# Sheet1.net
KiCad netlist of a schematic drawn in Altium Designer
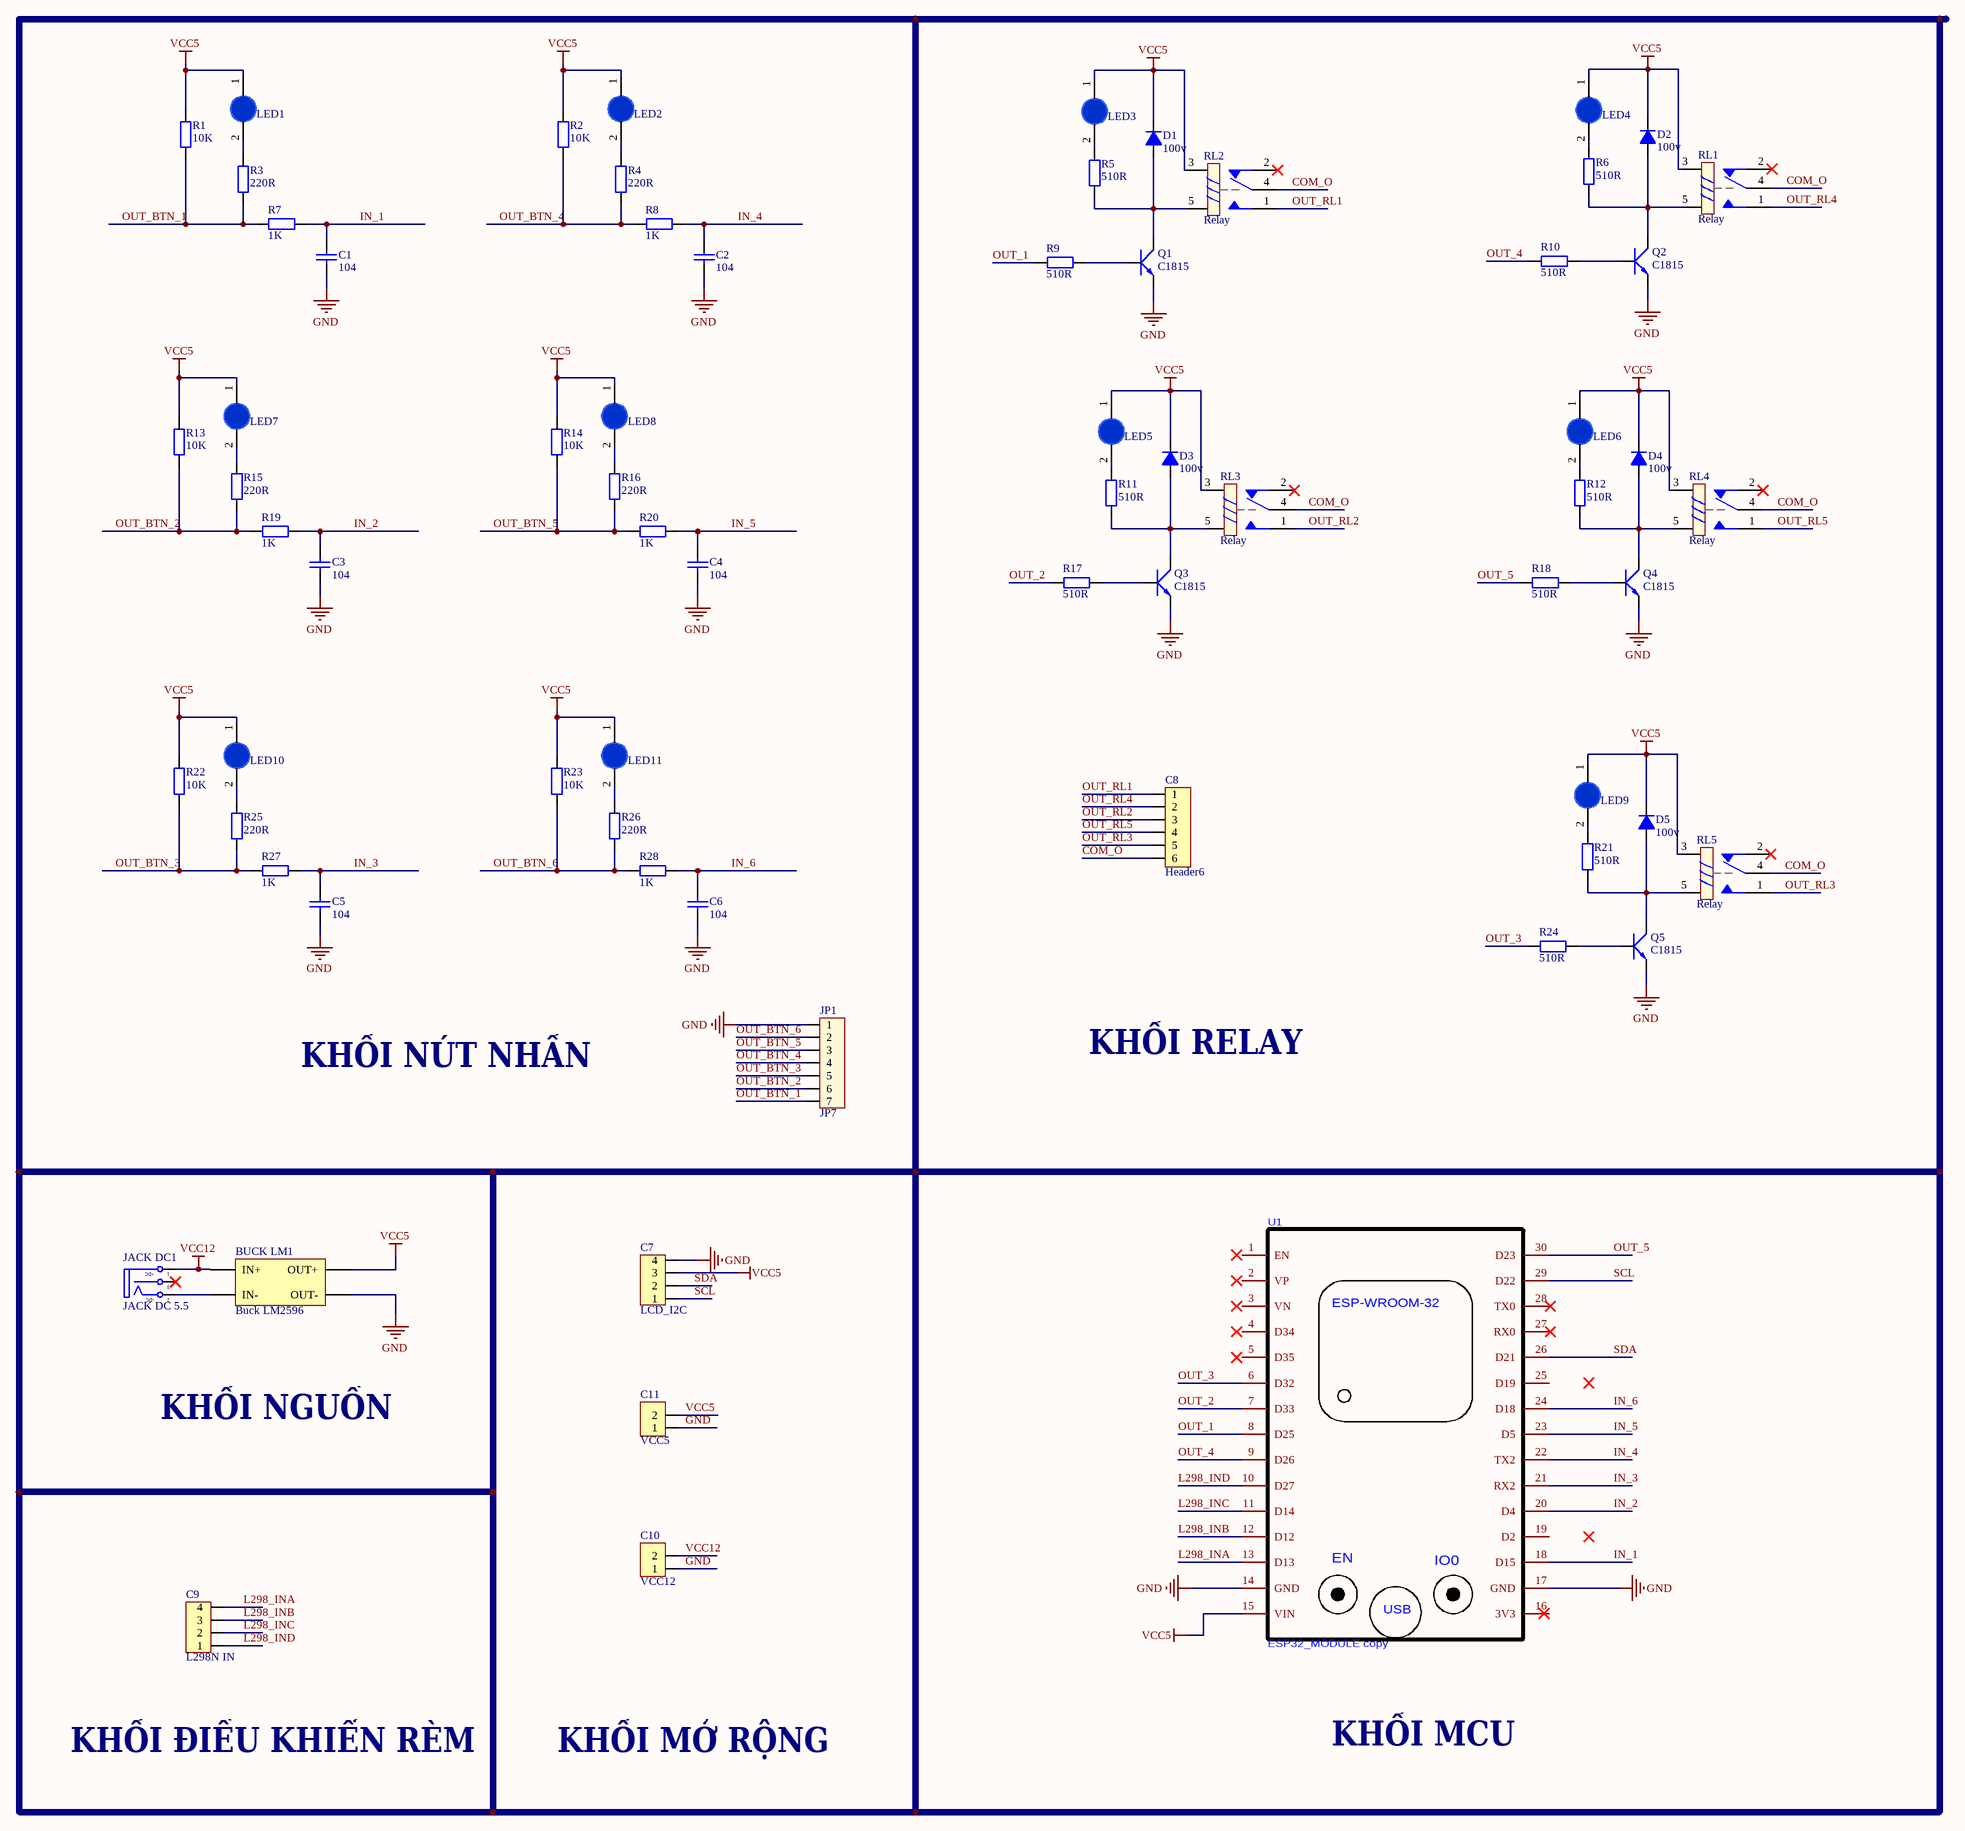
[diagram p0: Sheet1.SchDoc]

(export (version "E")
  (design (tool "Eeschema 10.0.6"))
  (components
    (comp (ref "BUCK LM1")
      (value "Buck LM2596")
      (footprint "BUCK LM2596")
      (libsource (lib "myLib_v1") (part "Buck LM2596"))
    )
    (comp (ref "C1")
      (value "104")
      (footprint "tu gom")
      (description "Cắm")
      (libsource (lib "Altium_Lib_by_KhueNguyenCreator") (part "Tu gom 104 50V"))
    )
    (comp (ref "C2")
      (value "104")
      (footprint "tu gom")
      (description "Cắm")
      (libsource (lib "Altium_Lib_by_KhueNguyenCreator") (part "Tu gom 104 50V"))
    )
    (comp (ref "C3")
      (value "104")
      (footprint "tu gom")
      (description "Cắm")
      (libsource (lib "Altium_Lib_by_KhueNguyenCreator") (part "Tu gom 104 50V"))
    )
    (comp (ref "C4")
      (value "104")
      (footprint "tu gom")
      (description "Cắm")
      (libsource (lib "Altium_Lib_by_KhueNguyenCreator") (part "Tu gom 104 50V"))
    )
    (comp (ref "C5")
      (value "104")
      (footprint "tu gom")
      (description "Cắm")
      (libsource (lib "Altium_Lib_by_KhueNguyenCreator") (part "Tu gom 104 50V"))
    )
    (comp (ref "C6")
      (value "104")
      (footprint "tu gom")
      (description "Cắm")
      (libsource (lib "Altium_Lib_by_KhueNguyenCreator") (part "Tu gom 104 50V"))
    )
    (comp (ref "C7")
      (value "LCD_I2C")
      (footprint "Header4")
      (description "Header IDC, 4 x 1 Pin Vertical 2.54mm Pitch (Non-Boxed, Male)")
      (fields
        (field (name "MANUFACTURER") "Würth Elektronik eiSos GmbH")
        (field (name "PARTNO") "613002143121")
        (field (name "CREATED BY") "Karrer Zheng")
      )
      (libsource (lib "myLib_v1") (part "Header4"))
    )
    (comp (ref "C8")
      (value "Header6")
      (footprint "Header6")
      (description "Header IDC, 6 x 1 Pin Vertical 2.54mm Pitch (Non-Boxed, Male)")
      (fields
        (field (name "MANUFACTURER") "Würth Elektronik eiSos GmbH")
        (field (name "PARTNO") "613002143121")
        (field (name "CREATED BY") "Karrer Zheng")
      )
      (libsource (lib "myLib_v1") (part "Header6"))
    )
    (comp (ref "C9")
      (value "L298N IN")
      (footprint "Header4")
      (description "Header IDC, 4 x 1 Pin Vertical 2.54mm Pitch (Non-Boxed, Male)")
      (fields
        (field (name "MANUFACTURER") "Würth Elektronik eiSos GmbH")
        (field (name "PARTNO") "613002143121")
        (field (name "CREATED BY") "Karrer Zheng")
      )
      (libsource (lib "myLib_v1") (part "Header4"))
    )
    (comp (ref "C10")
      (value "VCC12")
      (footprint "Header2")
      (description "Header IDC, 2 x 1 Pin Vertical 2.54mm Pitch (Non-Boxed, Male)")
      (fields
        (field (name "MANUFACTURER") "Würth Elektronik eiSos GmbH")
        (field (name "PARTNO") "613002143121")
        (field (name "CREATED BY") "Karrer Zheng")
      )
      (libsource (lib "myLib_v1") (part "Header2"))
    )
    (comp (ref "C11")
      (value "VCC5")
      (footprint "Header2")
      (description "Header IDC, 2 x 1 Pin Vertical 2.54mm Pitch (Non-Boxed, Male)")
      (fields
        (field (name "MANUFACTURER") "Würth Elektronik eiSos GmbH")
        (field (name "PARTNO") "613002143121")
        (field (name "CREATED BY") "Karrer Zheng")
      )
      (libsource (lib "myLib_v1") (part "Header2"))
    )
    (comp (ref "D1")
      (value "100v")
      (footprint "DIODE 0.5A")
      (description "Cắm")
      (libsource (lib "Altium_Lib_by_KhueNguyenCreator") (part "Diode 1N4148"))
    )
    (comp (ref "D2")
      (value "100v")
      (footprint "DIODE 0.5A")
      (description "Cắm")
      (libsource (lib "Altium_Lib_by_KhueNguyenCreator") (part "Diode 1N4148"))
    )
    (comp (ref "D3")
      (value "100v")
      (footprint "DIODE 0.5A")
      (description "Cắm")
      (libsource (lib "Altium_Lib_by_KhueNguyenCreator") (part "Diode 1N4148"))
    )
    (comp (ref "D4")
      (value "100v")
      (footprint "DIODE 0.5A")
      (description "Cắm")
      (libsource (lib "Altium_Lib_by_KhueNguyenCreator") (part "Diode 1N4148"))
    )
    (comp (ref "D5")
      (value "100v")
      (footprint "DIODE 0.5A")
      (description "Cắm")
      (libsource (lib "Altium_Lib_by_KhueNguyenCreator") (part "Diode 1N4148"))
    )
    (comp (ref "JACK DC1")
      (value "JACK DC 5.5")
      (footprint "JACK DC 5.5")
      (libsource (lib "Altium_Lib_by_KhueNguyenCreator") (part "JACK DC 5.5"))
    )
    (comp (ref "JP1")
      (value "JP7")
      (footprint "Header7")
      (description "Connector 7")
      (libsource (lib "myLib_v1") (part "Header7"))
    )
    (comp (ref "LED1")
      (value "LED 3mm")
      (footprint "LED-3MM-BLUE")
      (description "Cắm")
      (libsource (lib "myLib_v1") (part "LED 3mm Xanh Duong"))
    )
    (comp (ref "LED2")
      (value "LED 3mm")
      (footprint "LED-3MM-BLUE")
      (description "Cắm")
      (libsource (lib "myLib_v1") (part "LED 3mm Xanh Duong"))
    )
    (comp (ref "LED3")
      (value "LED 3mm")
      (footprint "LED-3MM-BLUE")
      (description "Cắm")
      (libsource (lib "myLib_v1") (part "LED 3mm Xanh Duong"))
    )
    (comp (ref "LED4")
      (value "LED 3mm")
      (footprint "LED-3MM-BLUE")
      (description "Cắm")
      (libsource (lib "myLib_v1") (part "LED 3mm Xanh Duong"))
    )
    (comp (ref "LED5")
      (value "LED 3mm")
      (footprint "LED-3MM-BLUE")
      (description "Cắm")
      (libsource (lib "myLib_v1") (part "LED 3mm Xanh Duong"))
    )
    (comp (ref "LED6")
      (value "LED 3mm")
      (footprint "LED-3MM-BLUE")
      (description "Cắm")
      (libsource (lib "myLib_v1") (part "LED 3mm Xanh Duong"))
    )
    (comp (ref "LED7")
      (value "LED 3mm")
      (footprint "LED-3MM-BLUE")
      (description "Cắm")
      (libsource (lib "myLib_v1") (part "LED 3mm Xanh Duong"))
    )
    (comp (ref "LED8")
      (value "LED 3mm")
      (footprint "LED-3MM-BLUE")
      (description "Cắm")
      (libsource (lib "myLib_v1") (part "LED 3mm Xanh Duong"))
    )
    (comp (ref "LED9")
      (value "LED 3mm")
      (footprint "LED-3MM-BLUE")
      (description "Cắm")
      (libsource (lib "myLib_v1") (part "LED 3mm Xanh Duong"))
    )
    (comp (ref "LED10")
      (value "LED 3mm")
      (footprint "LED-3MM-BLUE")
      (description "Cắm")
      (libsource (lib "myLib_v1") (part "LED 3mm Xanh Duong"))
    )
    (comp (ref "LED11")
      (value "LED 3mm")
      (footprint "LED-3MM-BLUE")
      (description "Cắm")
      (libsource (lib "myLib_v1") (part "LED 3mm Xanh Duong"))
    )
    (comp (ref "Q1")
      (value "C1815")
      (footprint "C1815_cam")
      (description "NPN 600mW, ECB")
      (libsource (lib "myLib_v1") (part "C1815"))
    )
    (comp (ref "Q2")
      (value "C1815")
      (footprint "C1815_cam")
      (description "NPN 600mW, ECB")
      (libsource (lib "myLib_v1") (part "C1815"))
    )
    (comp (ref "Q3")
      (value "C1815")
      (footprint "C1815_cam")
      (description "NPN 600mW, ECB")
      (libsource (lib "myLib_v1") (part "C1815"))
    )
    (comp (ref "Q4")
      (value "C1815")
      (footprint "C1815_cam")
      (description "NPN 600mW, ECB")
      (libsource (lib "myLib_v1") (part "C1815"))
    )
    (comp (ref "Q5")
      (value "C1815")
      (footprint "C1815_cam")
      (description "NPN 600mW, ECB")
      (libsource (lib "myLib_v1") (part "C1815"))
    )
    (comp (ref "R1")
      (value "10K")
      (footprint "R1/4W")
      (description "Resistor 1/4W")
      (libsource (lib "myLib_v1") (part "R1/4W"))
    )
    (comp (ref "R2")
      (value "10K")
      (footprint "R1/4W")
      (description "Resistor 1/4W")
      (libsource (lib "myLib_v1") (part "R1/4W"))
    )
    (comp (ref "R3")
      (value "220R")
      (footprint "R1/4W")
      (description "Resistor 1/4W")
      (libsource (lib "myLib_v1") (part "R1/4W"))
    )
    (comp (ref "R4")
      (value "220R")
      (footprint "R1/4W")
      (description "Resistor 1/4W")
      (libsource (lib "myLib_v1") (part "R1/4W"))
    )
    (comp (ref "R5")
      (value "510R")
      (footprint "R1/4W")
      (description "Resistor 1/4W")
      (libsource (lib "myLib_v1") (part "R1/4W"))
    )
    (comp (ref "R6")
      (value "510R")
      (footprint "R1/4W")
      (description "Resistor 1/4W")
      (libsource (lib "myLib_v1") (part "R1/4W"))
    )
    (comp (ref "R7")
      (value "1K")
      (footprint "R1/4W")
      (description "Resistor 1/4W")
      (libsource (lib "myLib_v1") (part "R1/4W"))
    )
    (comp (ref "R8")
      (value "1K")
      (footprint "R1/4W")
      (description "Resistor 1/4W")
      (libsource (lib "myLib_v1") (part "R1/4W"))
    )
    (comp (ref "R9")
      (value "510R")
      (footprint "R1/4W")
      (description "Resistor 1/4W")
      (libsource (lib "myLib_v1") (part "R1/4W"))
    )
    (comp (ref "R10")
      (value "510R")
      (footprint "R1/4W")
      (description "Resistor 1/4W")
      (libsource (lib "myLib_v1") (part "R1/4W"))
    )
    (comp (ref "R11")
      (value "510R")
      (footprint "R1/4W")
      (description "Resistor 1/4W")
      (libsource (lib "myLib_v1") (part "R1/4W"))
    )
    (comp (ref "R12")
      (value "510R")
      (footprint "R1/4W")
      (description "Resistor 1/4W")
      (libsource (lib "myLib_v1") (part "R1/4W"))
    )
    (comp (ref "R13")
      (value "10K")
      (footprint "R1/4W")
      (description "Resistor 1/4W")
      (libsource (lib "myLib_v1") (part "R1/4W"))
    )
    (comp (ref "R14")
      (value "10K")
      (footprint "R1/4W")
      (description "Resistor 1/4W")
      (libsource (lib "myLib_v1") (part "R1/4W"))
    )
    (comp (ref "R15")
      (value "220R")
      (footprint "R1/4W")
      (description "Resistor 1/4W")
      (libsource (lib "myLib_v1") (part "R1/4W"))
    )
    (comp (ref "R16")
      (value "220R")
      (footprint "R1/4W")
      (description "Resistor 1/4W")
      (libsource (lib "myLib_v1") (part "R1/4W"))
    )
    (comp (ref "R17")
      (value "510R")
      (footprint "R1/4W")
      (description "Resistor 1/4W")
      (libsource (lib "myLib_v1") (part "R1/4W"))
    )
    (comp (ref "R18")
      (value "510R")
      (footprint "R1/4W")
      (description "Resistor 1/4W")
      (libsource (lib "myLib_v1") (part "R1/4W"))
    )
    (comp (ref "R19")
      (value "1K")
      (footprint "R1/4W")
      (description "Resistor 1/4W")
      (libsource (lib "myLib_v1") (part "R1/4W"))
    )
    (comp (ref "R20")
      (value "1K")
      (footprint "R1/4W")
      (description "Resistor 1/4W")
      (libsource (lib "myLib_v1") (part "R1/4W"))
    )
    (comp (ref "R21")
      (value "510R")
      (footprint "R1/4W")
      (description "Resistor 1/4W")
      (libsource (lib "myLib_v1") (part "R1/4W"))
    )
    (comp (ref "R22")
      (value "10K")
      (footprint "R1/4W")
      (description "Resistor 1/4W")
      (libsource (lib "myLib_v1") (part "R1/4W"))
    )
    (comp (ref "R23")
      (value "10K")
      (footprint "R1/4W")
      (description "Resistor 1/4W")
      (libsource (lib "myLib_v1") (part "R1/4W"))
    )
    (comp (ref "R24")
      (value "510R")
      (footprint "R1/4W")
      (description "Resistor 1/4W")
      (libsource (lib "myLib_v1") (part "R1/4W"))
    )
    (comp (ref "R25")
      (value "220R")
      (footprint "R1/4W")
      (description "Resistor 1/4W")
      (libsource (lib "myLib_v1") (part "R1/4W"))
    )
    (comp (ref "R26")
      (value "220R")
      (footprint "R1/4W")
      (description "Resistor 1/4W")
      (libsource (lib "myLib_v1") (part "R1/4W"))
    )
    (comp (ref "R27")
      (value "1K")
      (footprint "R1/4W")
      (description "Resistor 1/4W")
      (libsource (lib "myLib_v1") (part "R1/4W"))
    )
    (comp (ref "R28")
      (value "1K")
      (footprint "R1/4W")
      (description "Resistor 1/4W")
      (libsource (lib "myLib_v1") (part "R1/4W"))
    )
    (comp (ref "RL1")
      (value "Relay")
      (footprint "RELAY_SRA_05VDC_SL_C")
      (description "Relay 5 Chan")
      (libsource (lib "myLib_v1") (part "RL_SRA-05VDC-SL-C"))
    )
    (comp (ref "RL2")
      (value "Relay")
      (footprint "RELAY_SRA_05VDC_SL_C")
      (description "Relay 5 Chan")
      (libsource (lib "myLib_v1") (part "RL_SRA-05VDC-SL-C"))
    )
    (comp (ref "RL3")
      (value "Relay")
      (footprint "RELAY_SRA_05VDC_SL_C")
      (description "Relay 5 Chan")
      (libsource (lib "myLib_v1") (part "RL_SRA-05VDC-SL-C"))
    )
    (comp (ref "RL4")
      (value "Relay")
      (footprint "RELAY_SRA_05VDC_SL_C")
      (description "Relay 5 Chan")
      (libsource (lib "myLib_v1") (part "RL_SRA-05VDC-SL-C"))
    )
    (comp (ref "RL5")
      (value "Relay")
      (footprint "RELAY_SRA_05VDC_SL_C")
      (description "Relay 5 Chan")
      (libsource (lib "myLib_v1") (part "RL_SRA-05VDC-SL-C"))
    )
    (comp (ref "U1")
      (value "ESP32_MODULE copy")
      (footprint "ESP32-WIFIMODULE-FOOTPRINT")
      (libsource (lib "myLib_v1") (part "ESP32_MODULE copy"))
    )
  )
  (nets
    (net (code "1") (name "/COM_O") (class "Default")
      (node (ref "C8") (pin "6") (pinfunction "6_6") (pintype "passive"))
      (node (ref "RL1") (pin "4") (pinfunction "4_4") (pintype "passive"))
      (node (ref "RL2") (pin "4") (pinfunction "4_4") (pintype "passive"))
      (node (ref "RL3") (pin "4") (pinfunction "4_4") (pintype "passive"))
      (node (ref "RL4") (pin "4") (pinfunction "4_4") (pintype "passive"))
      (node (ref "RL5") (pin "4") (pinfunction "4_4") (pintype "passive"))
    )
    (net (code "2") (name "/IN_1") (class "Default")
      (node (ref "C1") (pin "1") (pinfunction "1_1") (pintype "passive"))
      (node (ref "R7") (pin "1") (pinfunction "1_1") (pintype "passive"))
      (node (ref "U1") (pin "18") (pinfunction "D15_18") (pintype "passive"))
    )
    (net (code "3") (name "/IN_2") (class "Default")
      (node (ref "C3") (pin "1") (pinfunction "1_1") (pintype "passive"))
      (node (ref "R19") (pin "1") (pinfunction "1_1") (pintype "passive"))
      (node (ref "U1") (pin "20") (pinfunction "D4_20") (pintype "passive"))
    )
    (net (code "4") (name "/IN_3") (class "Default")
      (node (ref "C5") (pin "1") (pinfunction "1_1") (pintype "passive"))
      (node (ref "R27") (pin "1") (pinfunction "1_1") (pintype "passive"))
      (node (ref "U1") (pin "21") (pinfunction "RX2_21") (pintype "passive"))
    )
    (net (code "5") (name "/IN_4") (class "Default")
      (node (ref "C2") (pin "1") (pinfunction "1_1") (pintype "passive"))
      (node (ref "R8") (pin "1") (pinfunction "1_1") (pintype "passive"))
      (node (ref "U1") (pin "22") (pinfunction "TX2_22") (pintype "passive"))
    )
    (net (code "6") (name "/IN_5") (class "Default")
      (node (ref "C4") (pin "1") (pinfunction "1_1") (pintype "passive"))
      (node (ref "R20") (pin "1") (pinfunction "1_1") (pintype "passive"))
      (node (ref "U1") (pin "23") (pinfunction "D5_23") (pintype "passive"))
    )
    (net (code "7") (name "/IN_6") (class "Default")
      (node (ref "C6") (pin "1") (pinfunction "1_1") (pintype "passive"))
      (node (ref "R28") (pin "1") (pinfunction "1_1") (pintype "passive"))
      (node (ref "U1") (pin "24") (pinfunction "D18_24") (pintype "passive"))
    )
    (net (code "8") (name "/L298_INA") (class "Default")
      (node (ref "C9") (pin "4") (pinfunction "4_4") (pintype "passive"))
      (node (ref "U1") (pin "13") (pinfunction "D13_13") (pintype "passive"))
    )
    (net (code "9") (name "/L298_INB") (class "Default")
      (node (ref "C9") (pin "3") (pinfunction "3_3") (pintype "passive"))
      (node (ref "U1") (pin "12") (pinfunction "D12_12") (pintype "passive"))
    )
    (net (code "10") (name "/L298_INC") (class "Default")
      (node (ref "C9") (pin "2") (pinfunction "2_2") (pintype "passive"))
      (node (ref "U1") (pin "11") (pinfunction "D14_11") (pintype "passive"))
    )
    (net (code "11") (name "/L298_IND") (class "Default")
      (node (ref "C9") (pin "1") (pinfunction "1_1") (pintype "passive"))
      (node (ref "U1") (pin "10") (pinfunction "D27_10") (pintype "passive"))
    )
    (net (code "12") (name "/OUT_1") (class "Default")
      (node (ref "R9") (pin "1") (pinfunction "1_1") (pintype "passive"))
      (node (ref "U1") (pin "8") (pinfunction "D25_8") (pintype "passive"))
    )
    (net (code "13") (name "/OUT_2") (class "Default")
      (node (ref "R17") (pin "1") (pinfunction "1_1") (pintype "passive"))
      (node (ref "U1") (pin "7") (pinfunction "D33_7") (pintype "passive"))
    )
    (net (code "14") (name "/OUT_3") (class "Default")
      (node (ref "R24") (pin "1") (pinfunction "1_1") (pintype "passive"))
      (node (ref "U1") (pin "6") (pinfunction "D32_6") (pintype "passive"))
    )
    (net (code "15") (name "/OUT_4") (class "Default")
      (node (ref "R10") (pin "1") (pinfunction "1_1") (pintype "passive"))
      (node (ref "U1") (pin "9") (pinfunction "D26_9") (pintype "passive"))
    )
    (net (code "16") (name "/OUT_5") (class "Default")
      (node (ref "R18") (pin "1") (pinfunction "1_1") (pintype "passive"))
      (node (ref "U1") (pin "30") (pinfunction "D23_30") (pintype "passive"))
    )
    (net (code "17") (name "/OUT_BTN_1") (class "Default")
      (node (ref "JP1") (pin "7") (pinfunction "7_7") (pintype "passive"))
      (node (ref "R1") (pin "1") (pinfunction "1_1") (pintype "passive"))
      (node (ref "R3") (pin "1") (pinfunction "1_1") (pintype "passive"))
      (node (ref "R7") (pin "2") (pinfunction "2_2") (pintype "passive"))
    )
    (net (code "18") (name "/OUT_BTN_2") (class "Default")
      (node (ref "JP1") (pin "6") (pinfunction "6_6") (pintype "passive"))
      (node (ref "R13") (pin "1") (pinfunction "1_1") (pintype "passive"))
      (node (ref "R15") (pin "1") (pinfunction "1_1") (pintype "passive"))
      (node (ref "R19") (pin "2") (pinfunction "2_2") (pintype "passive"))
    )
    (net (code "19") (name "/OUT_BTN_3") (class "Default")
      (node (ref "JP1") (pin "5") (pinfunction "5_5") (pintype "passive"))
      (node (ref "R22") (pin "1") (pinfunction "1_1") (pintype "passive"))
      (node (ref "R25") (pin "1") (pinfunction "1_1") (pintype "passive"))
      (node (ref "R27") (pin "2") (pinfunction "2_2") (pintype "passive"))
    )
    (net (code "20") (name "/OUT_BTN_4") (class "Default")
      (node (ref "JP1") (pin "4") (pinfunction "4_4") (pintype "passive"))
      (node (ref "R2") (pin "1") (pinfunction "1_1") (pintype "passive"))
      (node (ref "R4") (pin "1") (pinfunction "1_1") (pintype "passive"))
      (node (ref "R8") (pin "2") (pinfunction "2_2") (pintype "passive"))
    )
    (net (code "21") (name "/OUT_BTN_5") (class "Default")
      (node (ref "JP1") (pin "3") (pinfunction "3_3") (pintype "passive"))
      (node (ref "R14") (pin "1") (pinfunction "1_1") (pintype "passive"))
      (node (ref "R16") (pin "1") (pinfunction "1_1") (pintype "passive"))
      (node (ref "R20") (pin "2") (pinfunction "2_2") (pintype "passive"))
    )
    (net (code "22") (name "/OUT_BTN_6") (class "Default")
      (node (ref "JP1") (pin "2") (pinfunction "2_2") (pintype "passive"))
      (node (ref "R23") (pin "1") (pinfunction "1_1") (pintype "passive"))
      (node (ref "R26") (pin "1") (pinfunction "1_1") (pintype "passive"))
      (node (ref "R28") (pin "2") (pinfunction "2_2") (pintype "passive"))
    )
    (net (code "23") (name "/OUT_RL1") (class "Default")
      (node (ref "C8") (pin "1") (pinfunction "1_1") (pintype "passive"))
      (node (ref "RL2") (pin "1") (pinfunction "1_1") (pintype "passive"))
    )
    (net (code "24") (name "/OUT_RL2") (class "Default")
      (node (ref "C8") (pin "3") (pinfunction "3_3") (pintype "passive"))
      (node (ref "RL3") (pin "1") (pinfunction "1_1") (pintype "passive"))
    )
    (net (code "25") (name "/OUT_RL3") (class "Default")
      (node (ref "C8") (pin "5") (pinfunction "5_5") (pintype "passive"))
      (node (ref "RL5") (pin "1") (pinfunction "1_1") (pintype "passive"))
    )
    (net (code "26") (name "/OUT_RL4") (class "Default")
      (node (ref "C8") (pin "2") (pinfunction "2_2") (pintype "passive"))
      (node (ref "RL1") (pin "1") (pinfunction "1_1") (pintype "passive"))
    )
    (net (code "27") (name "/OUT_RL5") (class "Default")
      (node (ref "C8") (pin "4") (pinfunction "4_4") (pintype "passive"))
      (node (ref "RL4") (pin "1") (pinfunction "1_1") (pintype "passive"))
    )
    (net (code "28") (name "/SCL") (class "Default")
      (node (ref "C7") (pin "1") (pinfunction "1_1") (pintype "passive"))
      (node (ref "U1") (pin "29") (pinfunction "D22_29") (pintype "passive"))
    )
    (net (code "29") (name "/SDA") (class "Default")
      (node (ref "C7") (pin "2") (pinfunction "2_2") (pintype "passive"))
      (node (ref "U1") (pin "26") (pinfunction "D21_26") (pintype "passive"))
    )
    (net (code "30") (name "GND") (class "Default")
      (node (ref "BUCK LM1") (pin "3") (pinfunction "OUT-_3") (pintype "passive"))
      (node (ref "C1") (pin "2") (pinfunction "2_2") (pintype "passive"))
      (node (ref "C10") (pin "1") (pinfunction "1_1") (pintype "passive"))
      (node (ref "C11") (pin "1") (pinfunction "1_1") (pintype "passive"))
      (node (ref "C2") (pin "2") (pinfunction "2_2") (pintype "passive"))
      (node (ref "C3") (pin "2") (pinfunction "2_2") (pintype "passive"))
      (node (ref "C4") (pin "2") (pinfunction "2_2") (pintype "passive"))
      (node (ref "C5") (pin "2") (pinfunction "2_2") (pintype "passive"))
      (node (ref "C6") (pin "2") (pinfunction "2_2") (pintype "passive"))
      (node (ref "C7") (pin "4") (pinfunction "4_4") (pintype "passive"))
      (node (ref "JP1") (pin "1") (pinfunction "1_1") (pintype "passive"))
      (node (ref "Q1") (pin "1") (pinfunction "E_1") (pintype "passive"))
      (node (ref "Q2") (pin "1") (pinfunction "E_1") (pintype "passive"))
      (node (ref "Q3") (pin "1") (pinfunction "E_1") (pintype "passive"))
      (node (ref "Q4") (pin "1") (pinfunction "E_1") (pintype "passive"))
      (node (ref "Q5") (pin "1") (pinfunction "E_1") (pintype "passive"))
      (node (ref "U1") (pin "14") (pinfunction "GND_14") (pintype "passive"))
      (node (ref "U1") (pin "17") (pinfunction "GND_17") (pintype "passive"))
    )
    (net (code "31") (name "Net-(BUCK LM1-IN-)") (class "Default")
      (node (ref "BUCK LM1") (pin "2") (pinfunction "IN-_2") (pintype "passive"))
      (node (ref "JACK DC1") (pin "2") (pinfunction "TN_2") (pintype "passive"))
    )
    (net (code "32") (name "Net-(D1-A)") (class "Default")
      (node (ref "D1") (pin "1") (pinfunction "A_1") (pintype "passive"))
      (node (ref "Q1") (pin "2") (pinfunction "C_2") (pintype "passive"))
      (node (ref "R5") (pin "2") (pinfunction "2_2") (pintype "passive"))
      (node (ref "RL2") (pin "5") (pinfunction "5_5") (pintype "passive"))
    )
    (net (code "33") (name "Net-(D2-A)") (class "Default")
      (node (ref "D2") (pin "1") (pinfunction "A_1") (pintype "passive"))
      (node (ref "Q2") (pin "2") (pinfunction "C_2") (pintype "passive"))
      (node (ref "R6") (pin "2") (pinfunction "2_2") (pintype "passive"))
      (node (ref "RL1") (pin "5") (pinfunction "5_5") (pintype "passive"))
    )
    (net (code "34") (name "Net-(D3-A)") (class "Default")
      (node (ref "D3") (pin "1") (pinfunction "A_1") (pintype "passive"))
      (node (ref "Q3") (pin "2") (pinfunction "C_2") (pintype "passive"))
      (node (ref "R11") (pin "2") (pinfunction "2_2") (pintype "passive"))
      (node (ref "RL3") (pin "5") (pinfunction "5_5") (pintype "passive"))
    )
    (net (code "35") (name "Net-(D4-A)") (class "Default")
      (node (ref "D4") (pin "1") (pinfunction "A_1") (pintype "passive"))
      (node (ref "Q4") (pin "2") (pinfunction "C_2") (pintype "passive"))
      (node (ref "R12") (pin "2") (pinfunction "2_2") (pintype "passive"))
      (node (ref "RL4") (pin "5") (pinfunction "5_5") (pintype "passive"))
    )
    (net (code "36") (name "Net-(D5-A)") (class "Default")
      (node (ref "D5") (pin "1") (pinfunction "A_1") (pintype "passive"))
      (node (ref "Q5") (pin "2") (pinfunction "C_2") (pintype "passive"))
      (node (ref "R21") (pin "2") (pinfunction "2_2") (pintype "passive"))
      (node (ref "RL5") (pin "5") (pinfunction "5_5") (pintype "passive"))
    )
    (net (code "37") (name "Net-(LED1-K)") (class "Default")
      (node (ref "LED1") (pin "2") (pinfunction "K_2") (pintype "passive"))
      (node (ref "R3") (pin "2") (pinfunction "2_2") (pintype "passive"))
    )
    (net (code "38") (name "Net-(LED2-K)") (class "Default")
      (node (ref "LED2") (pin "2") (pinfunction "K_2") (pintype "passive"))
      (node (ref "R4") (pin "2") (pinfunction "2_2") (pintype "passive"))
    )
    (net (code "39") (name "Net-(LED3-K)") (class "Default")
      (node (ref "LED3") (pin "2") (pinfunction "K_2") (pintype "passive"))
      (node (ref "R5") (pin "1") (pinfunction "1_1") (pintype "passive"))
    )
    (net (code "40") (name "Net-(LED4-K)") (class "Default")
      (node (ref "LED4") (pin "2") (pinfunction "K_2") (pintype "passive"))
      (node (ref "R6") (pin "1") (pinfunction "1_1") (pintype "passive"))
    )
    (net (code "41") (name "Net-(LED5-K)") (class "Default")
      (node (ref "LED5") (pin "2") (pinfunction "K_2") (pintype "passive"))
      (node (ref "R11") (pin "1") (pinfunction "1_1") (pintype "passive"))
    )
    (net (code "42") (name "Net-(LED6-K)") (class "Default")
      (node (ref "LED6") (pin "2") (pinfunction "K_2") (pintype "passive"))
      (node (ref "R12") (pin "1") (pinfunction "1_1") (pintype "passive"))
    )
    (net (code "43") (name "Net-(LED7-K)") (class "Default")
      (node (ref "LED7") (pin "2") (pinfunction "K_2") (pintype "passive"))
      (node (ref "R15") (pin "2") (pinfunction "2_2") (pintype "passive"))
    )
    (net (code "44") (name "Net-(LED8-K)") (class "Default")
      (node (ref "LED8") (pin "2") (pinfunction "K_2") (pintype "passive"))
      (node (ref "R16") (pin "2") (pinfunction "2_2") (pintype "passive"))
    )
    (net (code "45") (name "Net-(LED9-K)") (class "Default")
      (node (ref "LED9") (pin "2") (pinfunction "K_2") (pintype "passive"))
      (node (ref "R21") (pin "1") (pinfunction "1_1") (pintype "passive"))
    )
    (net (code "46") (name "Net-(LED10-K)") (class "Default")
      (node (ref "LED10") (pin "2") (pinfunction "K_2") (pintype "passive"))
      (node (ref "R25") (pin "2") (pinfunction "2_2") (pintype "passive"))
    )
    (net (code "47") (name "Net-(LED11-K)") (class "Default")
      (node (ref "LED11") (pin "2") (pinfunction "K_2") (pintype "passive"))
      (node (ref "R26") (pin "2") (pinfunction "2_2") (pintype "passive"))
    )
    (net (code "48") (name "Net-(Q1-B)") (class "Default")
      (node (ref "Q1") (pin "3") (pinfunction "B_3") (pintype "passive"))
      (node (ref "R9") (pin "2") (pinfunction "2_2") (pintype "passive"))
    )
    (net (code "49") (name "Net-(Q2-B)") (class "Default")
      (node (ref "Q2") (pin "3") (pinfunction "B_3") (pintype "passive"))
      (node (ref "R10") (pin "2") (pinfunction "2_2") (pintype "passive"))
    )
    (net (code "50") (name "Net-(Q3-B)") (class "Default")
      (node (ref "Q3") (pin "3") (pinfunction "B_3") (pintype "passive"))
      (node (ref "R17") (pin "2") (pinfunction "2_2") (pintype "passive"))
    )
    (net (code "51") (name "Net-(Q4-B)") (class "Default")
      (node (ref "Q4") (pin "3") (pinfunction "B_3") (pintype "passive"))
      (node (ref "R18") (pin "2") (pinfunction "2_2") (pintype "passive"))
    )
    (net (code "52") (name "Net-(Q5-B)") (class "Default")
      (node (ref "Q5") (pin "3") (pinfunction "B_3") (pintype "passive"))
      (node (ref "R24") (pin "2") (pinfunction "2_2") (pintype "passive"))
    )
    (net (code "53") (name "VCC5") (class "Default")
      (node (ref "BUCK LM1") (pin "4") (pinfunction "OUT+_4") (pintype "passive"))
      (node (ref "C11") (pin "2") (pinfunction "2_2") (pintype "passive"))
      (node (ref "C7") (pin "3") (pinfunction "3_3") (pintype "passive"))
      (node (ref "D1") (pin "2") (pinfunction "K_2") (pintype "passive"))
      (node (ref "D2") (pin "2") (pinfunction "K_2") (pintype "passive"))
      (node (ref "D3") (pin "2") (pinfunction "K_2") (pintype "passive"))
      (node (ref "D4") (pin "2") (pinfunction "K_2") (pintype "passive"))
      (node (ref "D5") (pin "2") (pinfunction "K_2") (pintype "passive"))
      (node (ref "LED1") (pin "1") (pinfunction "A_1") (pintype "passive"))
      (node (ref "LED10") (pin "1") (pinfunction "A_1") (pintype "passive"))
      (node (ref "LED11") (pin "1") (pinfunction "A_1") (pintype "passive"))
      (node (ref "LED2") (pin "1") (pinfunction "A_1") (pintype "passive"))
      (node (ref "LED3") (pin "1") (pinfunction "A_1") (pintype "passive"))
      (node (ref "LED4") (pin "1") (pinfunction "A_1") (pintype "passive"))
      (node (ref "LED5") (pin "1") (pinfunction "A_1") (pintype "passive"))
      (node (ref "LED6") (pin "1") (pinfunction "A_1") (pintype "passive"))
      (node (ref "LED7") (pin "1") (pinfunction "A_1") (pintype "passive"))
      (node (ref "LED8") (pin "1") (pinfunction "A_1") (pintype "passive"))
      (node (ref "LED9") (pin "1") (pinfunction "A_1") (pintype "passive"))
      (node (ref "R1") (pin "2") (pinfunction "2_2") (pintype "passive"))
      (node (ref "R13") (pin "2") (pinfunction "2_2") (pintype "passive"))
      (node (ref "R14") (pin "2") (pinfunction "2_2") (pintype "passive"))
      (node (ref "R2") (pin "2") (pinfunction "2_2") (pintype "passive"))
      (node (ref "R22") (pin "2") (pinfunction "2_2") (pintype "passive"))
      (node (ref "R23") (pin "2") (pinfunction "2_2") (pintype "passive"))
      (node (ref "RL1") (pin "3") (pinfunction "3_3") (pintype "passive"))
      (node (ref "RL2") (pin "3") (pinfunction "3_3") (pintype "passive"))
      (node (ref "RL3") (pin "3") (pinfunction "3_3") (pintype "passive"))
      (node (ref "RL4") (pin "3") (pinfunction "3_3") (pintype "passive"))
      (node (ref "RL5") (pin "3") (pinfunction "3_3") (pintype "passive"))
      (node (ref "U1") (pin "15") (pinfunction "VIN_15") (pintype "passive"))
    )
    (net (code "54") (name "VCC12") (class "Default")
      (node (ref "BUCK LM1") (pin "1") (pinfunction "IN+_1") (pintype "passive"))
      (node (ref "C10") (pin "2") (pinfunction "2_2") (pintype "passive"))
      (node (ref "JACK DC1") (pin "1") (pinfunction "T_1") (pintype "passive"))
    )
    (net (code "55") (name "unconnected-(JACK DC1-S-Pad3)") (class "Default")
      (node (ref "JACK DC1") (pin "3") (pinfunction "S_3") (pintype "power_in+no_connect"))
    )
    (net (code "56") (name "unconnected-(RL1-Pad2)") (class "Default")
      (node (ref "RL1") (pin "2") (pinfunction "2_2") (pintype "passive+no_connect"))
    )
    (net (code "57") (name "unconnected-(RL2-Pad2)") (class "Default")
      (node (ref "RL2") (pin "2") (pinfunction "2_2") (pintype "passive+no_connect"))
    )
    (net (code "58") (name "unconnected-(RL3-Pad2)") (class "Default")
      (node (ref "RL3") (pin "2") (pinfunction "2_2") (pintype "passive+no_connect"))
    )
    (net (code "59") (name "unconnected-(RL4-Pad2)") (class "Default")
      (node (ref "RL4") (pin "2") (pinfunction "2_2") (pintype "passive+no_connect"))
    )
    (net (code "60") (name "unconnected-(RL5-Pad2)") (class "Default")
      (node (ref "RL5") (pin "2") (pinfunction "2_2") (pintype "passive+no_connect"))
    )
    (net (code "61") (name "unconnected-(U1-3V3-Pad16)") (class "Default")
      (node (ref "U1") (pin "16") (pinfunction "3V3_16") (pintype "passive"))
    )
    (net (code "62") (name "unconnected-(U1-D2-Pad19)") (class "Default")
      (node (ref "U1") (pin "19") (pinfunction "D2_19") (pintype "passive"))
    )
    (net (code "63") (name "unconnected-(U1-D19-Pad25)") (class "Default")
      (node (ref "U1") (pin "25") (pinfunction "D19_25") (pintype "passive"))
    )
    (net (code "64") (name "unconnected-(U1-D34-Pad4)") (class "Default")
      (node (ref "U1") (pin "4") (pinfunction "D34_4") (pintype "passive"))
    )
    (net (code "65") (name "unconnected-(U1-D35-Pad5)") (class "Default")
      (node (ref "U1") (pin "5") (pinfunction "D35_5") (pintype "passive"))
    )
    (net (code "66") (name "unconnected-(U1-EN-Pad1)") (class "Default")
      (node (ref "U1") (pin "1") (pinfunction "EN_1") (pintype "passive"))
    )
    (net (code "67") (name "unconnected-(U1-RX0-Pad27)") (class "Default")
      (node (ref "U1") (pin "27") (pinfunction "RX0_27") (pintype "passive"))
    )
    (net (code "68") (name "unconnected-(U1-TX0-Pad28)") (class "Default")
      (node (ref "U1") (pin "28") (pinfunction "TX0_28") (pintype "passive"))
    )
    (net (code "69") (name "unconnected-(U1-VN-Pad3)") (class "Default")
      (node (ref "U1") (pin "3") (pinfunction "VN_3") (pintype "passive"))
    )
    (net (code "70") (name "unconnected-(U1-VP-Pad2)") (class "Default")
      (node (ref "U1") (pin "2") (pinfunction "VP_2") (pintype "passive"))
    )
  )
)
